# ecg_prototype_2.net
KiCad netlist of a schematic drawn in EAGLE
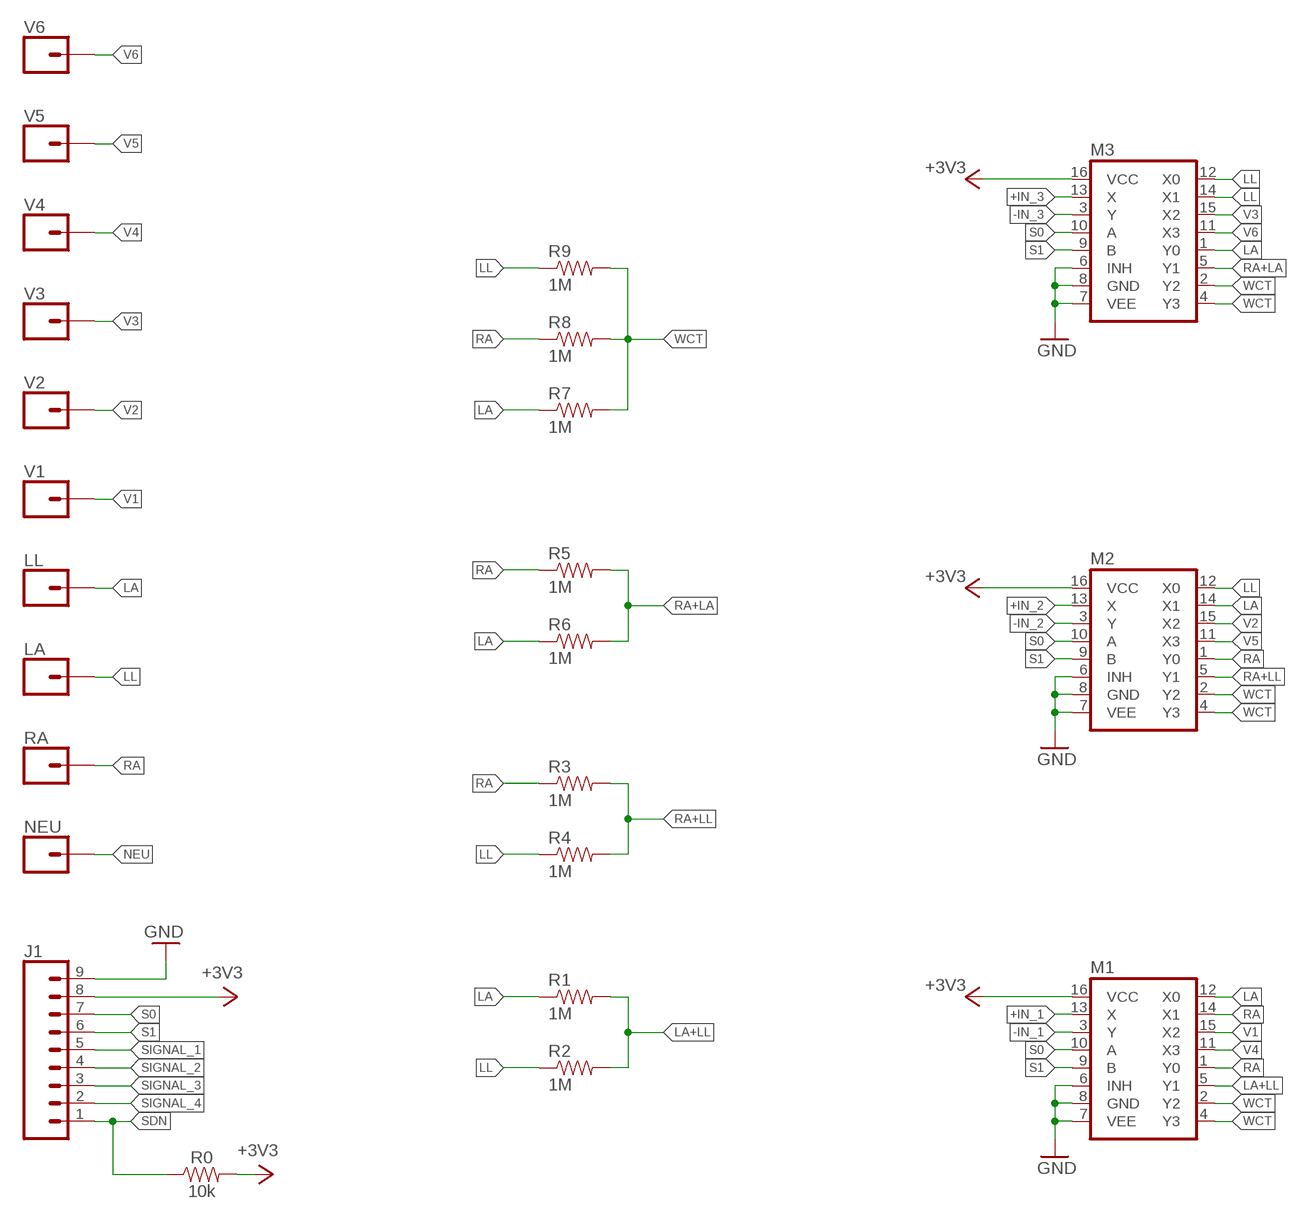
[diagram p0: schematic, sheet 1, part 1 of 2]
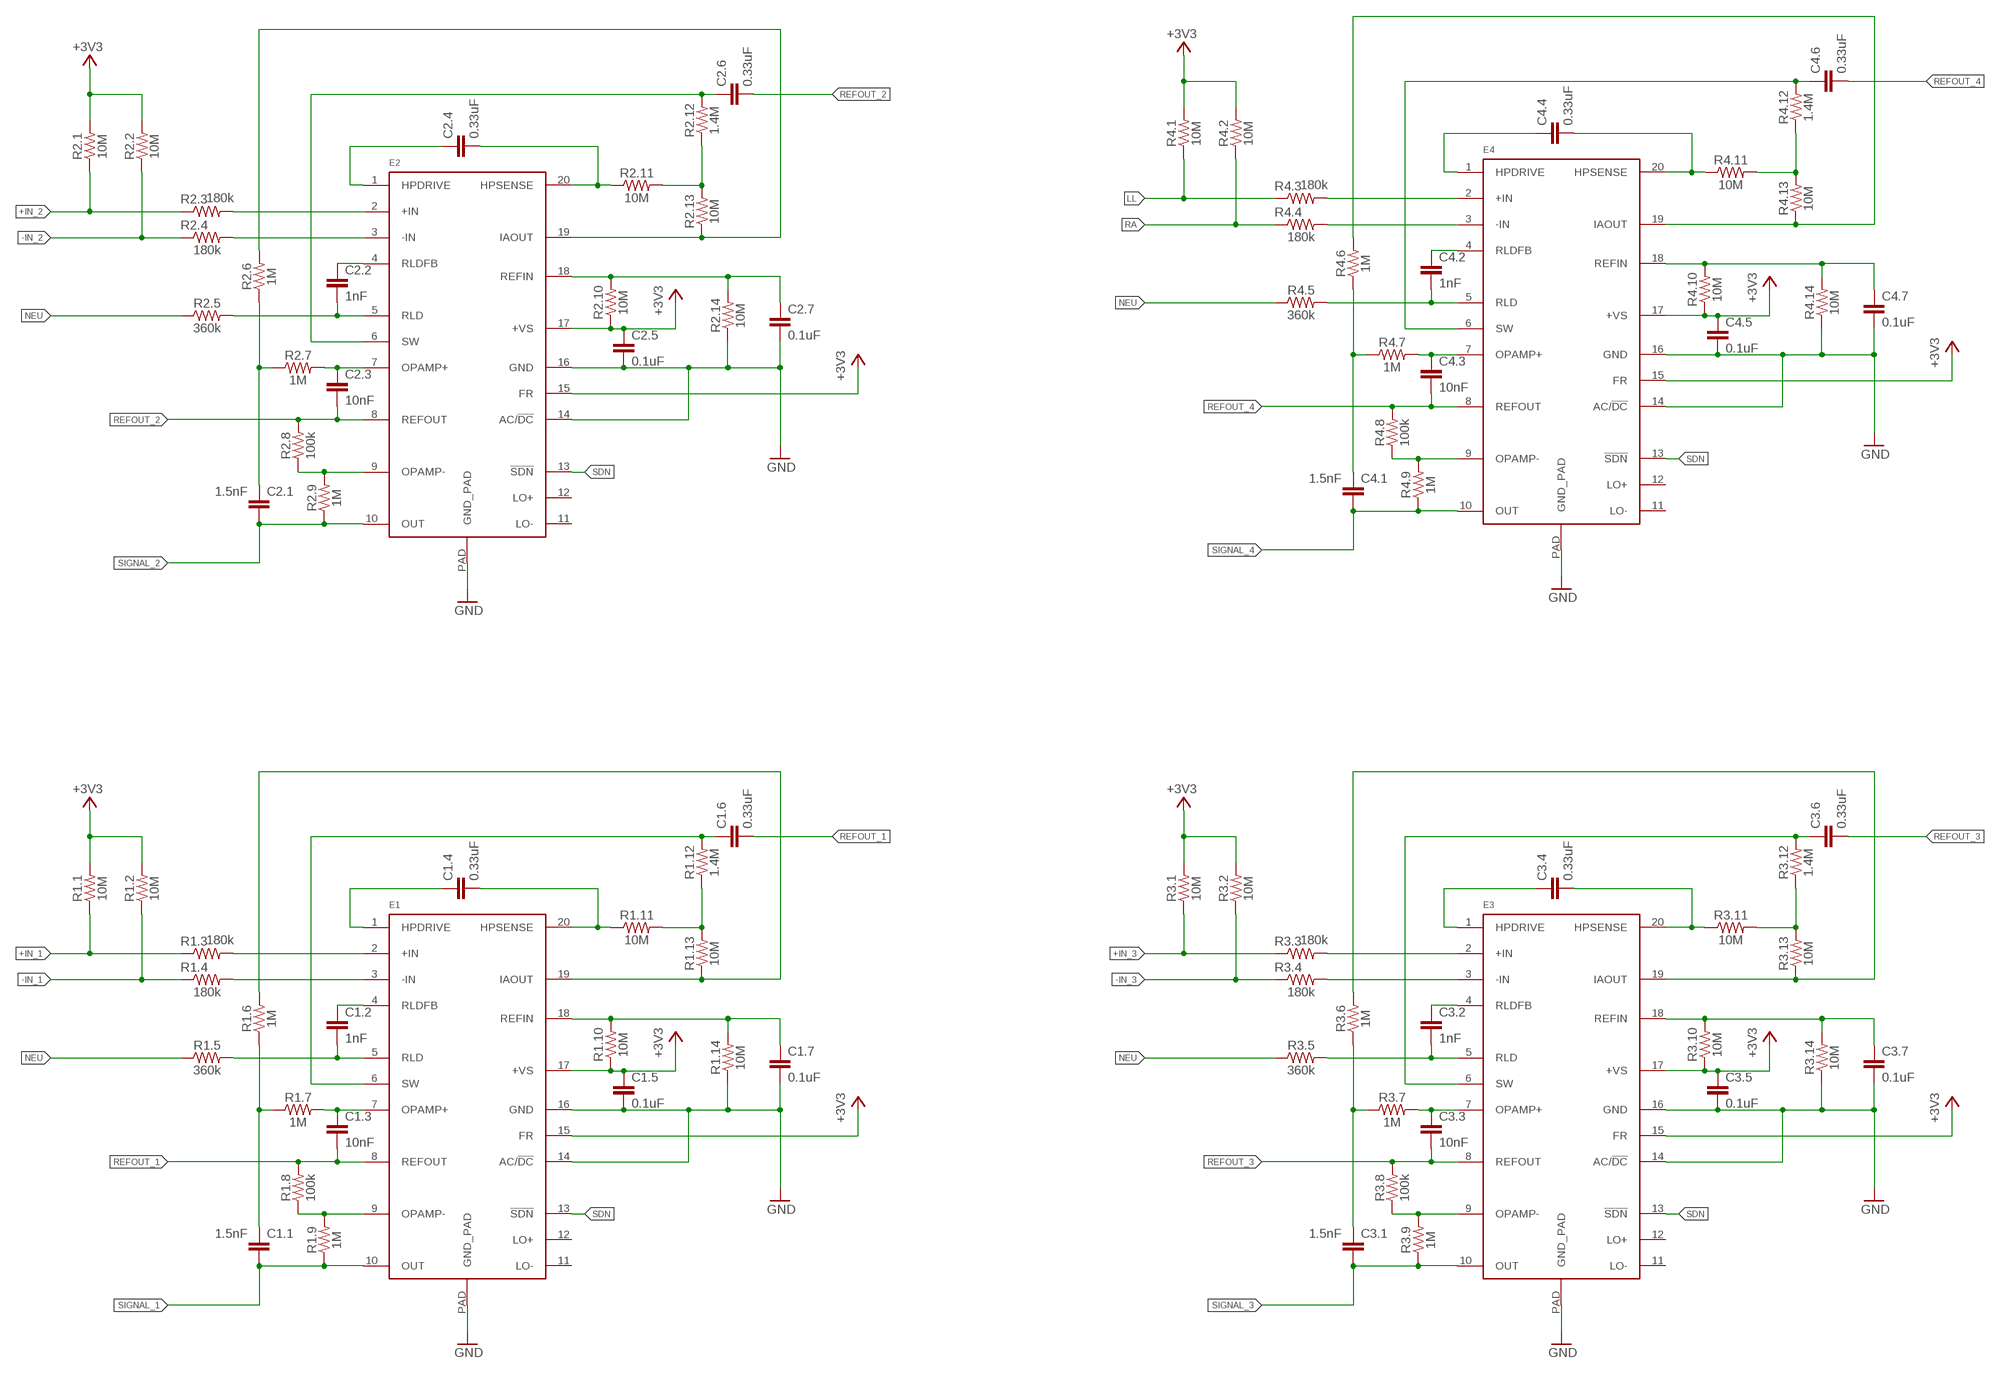
[diagram p1: schematic, sheet 1, part 2 of 2]

(export (version "E")
  (design (tool "Eeschema 10.0.6"))
  (components
    (comp (ref "C1.1")
      (value "1.5nF")
      (footprint "eagle-import:0603-CAP")
      (libsource (lib "eagle-import") (part "CAP0603-CAP"))
    )
    (comp (ref "C1.2")
      (value "1nF")
      (footprint "eagle-import:0603-CAP")
      (libsource (lib "eagle-import") (part "CAP0603-CAP"))
    )
    (comp (ref "C1.3")
      (value "10nF")
      (footprint "eagle-import:0603-CAP")
      (libsource (lib "eagle-import") (part "CAP0603-CAP"))
    )
    (comp (ref "C1.4")
      (value "0.33uF")
      (footprint "eagle-import:0805")
      (libsource (lib "eagle-import") (part "CAP0805"))
    )
    (comp (ref "C1.5")
      (value "0.1uF")
      (footprint "eagle-import:0603-CAP")
      (libsource (lib "eagle-import") (part "CAP0603-CAP"))
    )
    (comp (ref "C1.6")
      (value "0.33uF")
      (footprint "eagle-import:0805")
      (libsource (lib "eagle-import") (part "CAP0805"))
    )
    (comp (ref "C1.7")
      (value "0.1uF")
      (footprint "eagle-import:0603-CAP")
      (libsource (lib "eagle-import") (part "CAP0603-CAP"))
    )
    (comp (ref "C2.1")
      (value "1.5nF")
      (footprint "eagle-import:0603-CAP")
      (libsource (lib "eagle-import") (part "CAP0603-CAP"))
    )
    (comp (ref "C2.2")
      (value "1nF")
      (footprint "eagle-import:0603-CAP")
      (libsource (lib "eagle-import") (part "CAP0603-CAP"))
    )
    (comp (ref "C2.3")
      (value "10nF")
      (footprint "eagle-import:0603-CAP")
      (libsource (lib "eagle-import") (part "CAP0603-CAP"))
    )
    (comp (ref "C2.4")
      (value "0.33uF")
      (footprint "eagle-import:0805")
      (libsource (lib "eagle-import") (part "CAP0805"))
    )
    (comp (ref "C2.5")
      (value "0.1uF")
      (footprint "eagle-import:0603-CAP")
      (libsource (lib "eagle-import") (part "CAP0603-CAP"))
    )
    (comp (ref "C2.6")
      (value "0.33uF")
      (footprint "eagle-import:0805")
      (libsource (lib "eagle-import") (part "CAP0805"))
    )
    (comp (ref "C2.7")
      (value "0.1uF")
      (footprint "eagle-import:0603-CAP")
      (libsource (lib "eagle-import") (part "CAP0603-CAP"))
    )
    (comp (ref "C3.1")
      (value "1.5nF")
      (footprint "eagle-import:0603-CAP")
      (libsource (lib "eagle-import") (part "CAP0603-CAP"))
    )
    (comp (ref "C3.2")
      (value "1nF")
      (footprint "eagle-import:0603-CAP")
      (libsource (lib "eagle-import") (part "CAP0603-CAP"))
    )
    (comp (ref "C3.3")
      (value "10nF")
      (footprint "eagle-import:0603-CAP")
      (libsource (lib "eagle-import") (part "CAP0603-CAP"))
    )
    (comp (ref "C3.4")
      (value "0.33uF")
      (footprint "eagle-import:0805")
      (libsource (lib "eagle-import") (part "CAP0805"))
    )
    (comp (ref "C3.5")
      (value "0.1uF")
      (footprint "eagle-import:0603-CAP")
      (libsource (lib "eagle-import") (part "CAP0603-CAP"))
    )
    (comp (ref "C3.6")
      (value "0.33uF")
      (footprint "eagle-import:0805")
      (libsource (lib "eagle-import") (part "CAP0805"))
    )
    (comp (ref "C3.7")
      (value "0.1uF")
      (footprint "eagle-import:0603-CAP")
      (libsource (lib "eagle-import") (part "CAP0603-CAP"))
    )
    (comp (ref "C4.1")
      (value "1.5nF")
      (footprint "eagle-import:0603-CAP")
      (libsource (lib "eagle-import") (part "CAP0603-CAP"))
    )
    (comp (ref "C4.2")
      (value "1nF")
      (footprint "eagle-import:0603-CAP")
      (libsource (lib "eagle-import") (part "CAP0603-CAP"))
    )
    (comp (ref "C4.3")
      (value "10nF")
      (footprint "eagle-import:0603-CAP")
      (libsource (lib "eagle-import") (part "CAP0603-CAP"))
    )
    (comp (ref "C4.4")
      (value "0.33uF")
      (footprint "eagle-import:0805")
      (libsource (lib "eagle-import") (part "CAP0805"))
    )
    (comp (ref "C4.5")
      (value "0.1uF")
      (footprint "eagle-import:0603-CAP")
      (libsource (lib "eagle-import") (part "CAP0603-CAP"))
    )
    (comp (ref "C4.6")
      (value "0.33uF")
      (footprint "eagle-import:0805")
      (libsource (lib "eagle-import") (part "CAP0805"))
    )
    (comp (ref "C4.7")
      (value "0.1uF")
      (footprint "eagle-import:0603-CAP")
      (libsource (lib "eagle-import") (part "CAP0603-CAP"))
    )
    (comp (ref "E1")
      (value "AD8232ACPZ-R7")
      (footprint "eagle-import:LFCSP_20")
      (libsource (lib "eagle-import") (part "AD8232"))
    )
    (comp (ref "E2")
      (value "AD8232ACPZ-R7")
      (footprint "eagle-import:LFCSP_20")
      (libsource (lib "eagle-import") (part "AD8232"))
    )
    (comp (ref "E3")
      (value "AD8232ACPZ-R7")
      (footprint "eagle-import:LFCSP_20")
      (libsource (lib "eagle-import") (part "AD8232"))
    )
    (comp (ref "E4")
      (value "AD8232ACPZ-R7")
      (footprint "eagle-import:LFCSP_20")
      (libsource (lib "eagle-import") (part "AD8232"))
    )
    (comp (ref "J1")
      (value "CONN_09")
      (footprint "eagle-import:1X09")
      (libsource (lib "eagle-import") (part "CONN_09"))
    )
    (comp (ref "LA")
      (value "CONN_01")
      (footprint "eagle-import:1X01")
      (libsource (lib "eagle-import") (part "CONN_01"))
    )
    (comp (ref "LL")
      (value "CONN_01")
      (footprint "eagle-import:1X01")
      (libsource (lib "eagle-import") (part "CONN_01"))
    )
    (comp (ref "M1")
      (value "74HC4052D")
      (footprint "eagle-import:SO16")
      (libsource (lib "eagle-import") (part "744052DHC"))
    )
    (comp (ref "M2")
      (value "74HC4052D")
      (footprint "eagle-import:SO16")
      (libsource (lib "eagle-import") (part "744052DHC"))
    )
    (comp (ref "M3")
      (value "74HC4052D")
      (footprint "eagle-import:SO16")
      (libsource (lib "eagle-import") (part "744052DHC"))
    )
    (comp (ref "NEU")
      (value "CONN_01")
      (footprint "eagle-import:1X01")
      (libsource (lib "eagle-import") (part "CONN_01"))
    )
    (comp (ref "R0")
      (value "10k")
      (footprint "eagle-import:0603")
      (libsource (lib "eagle-import") (part "10KOHM-0603-1/10W-1%"))
    )
    (comp (ref "R1")
      (value "1M")
      (footprint "eagle-import:0402-RES")
      (libsource (lib "eagle-import") (part "RESISTOR0402-RES"))
    )
    (comp (ref "R1.1")
      (value "10M")
      (footprint "eagle-import:0603")
      (libsource (lib "eagle-import") (part "RESISTOR0603"))
    )
    (comp (ref "R1.2")
      (value "10M")
      (footprint "eagle-import:0603")
      (libsource (lib "eagle-import") (part "RESISTOR0603"))
    )
    (comp (ref "R1.3")
      (value "180k")
      (footprint "eagle-import:0603")
      (libsource (lib "eagle-import") (part "RESISTOR0603"))
    )
    (comp (ref "R1.4")
      (value "180k")
      (footprint "eagle-import:0603")
      (libsource (lib "eagle-import") (part "RESISTOR0603"))
    )
    (comp (ref "R1.5")
      (value "360k")
      (footprint "eagle-import:0603")
      (libsource (lib "eagle-import") (part "RESISTOR0603"))
    )
    (comp (ref "R1.6")
      (value "1M")
      (footprint "eagle-import:0603")
      (libsource (lib "eagle-import") (part "RESISTOR0603"))
    )
    (comp (ref "R1.7")
      (value "1M")
      (footprint "eagle-import:0603")
      (libsource (lib "eagle-import") (part "RESISTOR0603"))
    )
    (comp (ref "R1.8")
      (value "100k")
      (footprint "eagle-import:0603")
      (libsource (lib "eagle-import") (part "RESISTOR0603"))
    )
    (comp (ref "R1.9")
      (value "1M")
      (footprint "eagle-import:0603")
      (libsource (lib "eagle-import") (part "RESISTOR0603"))
    )
    (comp (ref "R1.10")
      (value "10M")
      (footprint "eagle-import:0603")
      (libsource (lib "eagle-import") (part "RESISTOR0603"))
    )
    (comp (ref "R1.11")
      (value "10M")
      (footprint "eagle-import:0603")
      (libsource (lib "eagle-import") (part "RESISTOR0603"))
    )
    (comp (ref "R1.12")
      (value "1.4M")
      (footprint "eagle-import:0603")
      (libsource (lib "eagle-import") (part "RESISTOR0603"))
    )
    (comp (ref "R1.13")
      (value "10M")
      (footprint "eagle-import:0603")
      (libsource (lib "eagle-import") (part "RESISTOR0603"))
    )
    (comp (ref "R1.14")
      (value "10M")
      (footprint "eagle-import:0603")
      (libsource (lib "eagle-import") (part "RESISTOR0603"))
    )
    (comp (ref "R2")
      (value "1M")
      (footprint "eagle-import:0402-RES")
      (libsource (lib "eagle-import") (part "RESISTOR0402-RES"))
    )
    (comp (ref "R2.1")
      (value "10M")
      (footprint "eagle-import:0603")
      (libsource (lib "eagle-import") (part "RESISTOR0603"))
    )
    (comp (ref "R2.2")
      (value "10M")
      (footprint "eagle-import:0603")
      (libsource (lib "eagle-import") (part "RESISTOR0603"))
    )
    (comp (ref "R2.3")
      (value "180k")
      (footprint "eagle-import:0603")
      (libsource (lib "eagle-import") (part "RESISTOR0603"))
    )
    (comp (ref "R2.4")
      (value "180k")
      (footprint "eagle-import:0603")
      (libsource (lib "eagle-import") (part "RESISTOR0603"))
    )
    (comp (ref "R2.5")
      (value "360k")
      (footprint "eagle-import:0603")
      (libsource (lib "eagle-import") (part "RESISTOR0603"))
    )
    (comp (ref "R2.6")
      (value "1M")
      (footprint "eagle-import:0603")
      (libsource (lib "eagle-import") (part "RESISTOR0603"))
    )
    (comp (ref "R2.7")
      (value "1M")
      (footprint "eagle-import:0603")
      (libsource (lib "eagle-import") (part "RESISTOR0603"))
    )
    (comp (ref "R2.8")
      (value "100k")
      (footprint "eagle-import:0603")
      (libsource (lib "eagle-import") (part "RESISTOR0603"))
    )
    (comp (ref "R2.9")
      (value "1M")
      (footprint "eagle-import:0603")
      (libsource (lib "eagle-import") (part "RESISTOR0603"))
    )
    (comp (ref "R2.10")
      (value "10M")
      (footprint "eagle-import:0603")
      (libsource (lib "eagle-import") (part "RESISTOR0603"))
    )
    (comp (ref "R2.11")
      (value "10M")
      (footprint "eagle-import:0603")
      (libsource (lib "eagle-import") (part "RESISTOR0603"))
    )
    (comp (ref "R2.12")
      (value "1.4M")
      (footprint "eagle-import:0603")
      (libsource (lib "eagle-import") (part "RESISTOR0603"))
    )
    (comp (ref "R2.13")
      (value "10M")
      (footprint "eagle-import:0603")
      (libsource (lib "eagle-import") (part "RESISTOR0603"))
    )
    (comp (ref "R2.14")
      (value "10M")
      (footprint "eagle-import:0603")
      (libsource (lib "eagle-import") (part "RESISTOR0603"))
    )
    (comp (ref "R3")
      (value "1M")
      (footprint "eagle-import:0402-RES")
      (libsource (lib "eagle-import") (part "RESISTOR0402-RES"))
    )
    (comp (ref "R3.1")
      (value "10M")
      (footprint "eagle-import:0603")
      (libsource (lib "eagle-import") (part "RESISTOR0603"))
    )
    (comp (ref "R3.2")
      (value "10M")
      (footprint "eagle-import:0603")
      (libsource (lib "eagle-import") (part "RESISTOR0603"))
    )
    (comp (ref "R3.3")
      (value "180k")
      (footprint "eagle-import:0603")
      (libsource (lib "eagle-import") (part "RESISTOR0603"))
    )
    (comp (ref "R3.4")
      (value "180k")
      (footprint "eagle-import:0603")
      (libsource (lib "eagle-import") (part "RESISTOR0603"))
    )
    (comp (ref "R3.5")
      (value "360k")
      (footprint "eagle-import:0603")
      (libsource (lib "eagle-import") (part "RESISTOR0603"))
    )
    (comp (ref "R3.6")
      (value "1M")
      (footprint "eagle-import:0603")
      (libsource (lib "eagle-import") (part "RESISTOR0603"))
    )
    (comp (ref "R3.7")
      (value "1M")
      (footprint "eagle-import:0603")
      (libsource (lib "eagle-import") (part "RESISTOR0603"))
    )
    (comp (ref "R3.8")
      (value "100k")
      (footprint "eagle-import:0603")
      (libsource (lib "eagle-import") (part "RESISTOR0603"))
    )
    (comp (ref "R3.9")
      (value "1M")
      (footprint "eagle-import:0603")
      (libsource (lib "eagle-import") (part "RESISTOR0603"))
    )
    (comp (ref "R3.10")
      (value "10M")
      (footprint "eagle-import:0603")
      (libsource (lib "eagle-import") (part "RESISTOR0603"))
    )
    (comp (ref "R3.11")
      (value "10M")
      (footprint "eagle-import:0603")
      (libsource (lib "eagle-import") (part "RESISTOR0603"))
    )
    (comp (ref "R3.12")
      (value "1.4M")
      (footprint "eagle-import:0603")
      (libsource (lib "eagle-import") (part "RESISTOR0603"))
    )
    (comp (ref "R3.13")
      (value "10M")
      (footprint "eagle-import:0603")
      (libsource (lib "eagle-import") (part "RESISTOR0603"))
    )
    (comp (ref "R3.14")
      (value "10M")
      (footprint "eagle-import:0603")
      (libsource (lib "eagle-import") (part "RESISTOR0603"))
    )
    (comp (ref "R4")
      (value "1M")
      (footprint "eagle-import:0402-RES")
      (libsource (lib "eagle-import") (part "RESISTOR0402-RES"))
    )
    (comp (ref "R4.1")
      (value "10M")
      (footprint "eagle-import:0603")
      (libsource (lib "eagle-import") (part "RESISTOR0603"))
    )
    (comp (ref "R4.2")
      (value "10M")
      (footprint "eagle-import:0603")
      (libsource (lib "eagle-import") (part "RESISTOR0603"))
    )
    (comp (ref "R4.3")
      (value "180k")
      (footprint "eagle-import:0603")
      (libsource (lib "eagle-import") (part "RESISTOR0603"))
    )
    (comp (ref "R4.4")
      (value "180k")
      (footprint "eagle-import:0603")
      (libsource (lib "eagle-import") (part "RESISTOR0603"))
    )
    (comp (ref "R4.5")
      (value "360k")
      (footprint "eagle-import:0603")
      (libsource (lib "eagle-import") (part "RESISTOR0603"))
    )
    (comp (ref "R4.6")
      (value "1M")
      (footprint "eagle-import:0603")
      (libsource (lib "eagle-import") (part "RESISTOR0603"))
    )
    (comp (ref "R4.7")
      (value "1M")
      (footprint "eagle-import:0603")
      (libsource (lib "eagle-import") (part "RESISTOR0603"))
    )
    (comp (ref "R4.8")
      (value "100k")
      (footprint "eagle-import:0603")
      (libsource (lib "eagle-import") (part "RESISTOR0603"))
    )
    (comp (ref "R4.9")
      (value "1M")
      (footprint "eagle-import:0603")
      (libsource (lib "eagle-import") (part "RESISTOR0603"))
    )
    (comp (ref "R4.10")
      (value "10M")
      (footprint "eagle-import:0603")
      (libsource (lib "eagle-import") (part "RESISTOR0603"))
    )
    (comp (ref "R4.11")
      (value "10M")
      (footprint "eagle-import:0603")
      (libsource (lib "eagle-import") (part "RESISTOR0603"))
    )
    (comp (ref "R4.12")
      (value "1.4M")
      (footprint "eagle-import:0603")
      (libsource (lib "eagle-import") (part "RESISTOR0603"))
    )
    (comp (ref "R4.13")
      (value "10M")
      (footprint "eagle-import:0603")
      (libsource (lib "eagle-import") (part "RESISTOR0603"))
    )
    (comp (ref "R4.14")
      (value "10M")
      (footprint "eagle-import:0603")
      (libsource (lib "eagle-import") (part "RESISTOR0603"))
    )
    (comp (ref "R5")
      (value "1M")
      (footprint "eagle-import:0402-RES")
      (libsource (lib "eagle-import") (part "RESISTOR0402-RES"))
    )
    (comp (ref "R6")
      (value "1M")
      (footprint "eagle-import:0402-RES")
      (libsource (lib "eagle-import") (part "RESISTOR0402-RES"))
    )
    (comp (ref "R7")
      (value "1M")
      (footprint "eagle-import:0402-RES")
      (libsource (lib "eagle-import") (part "RESISTOR0402-RES"))
    )
    (comp (ref "R8")
      (value "1M")
      (footprint "eagle-import:0402-RES")
      (libsource (lib "eagle-import") (part "RESISTOR0402-RES"))
    )
    (comp (ref "R9")
      (value "1M")
      (footprint "eagle-import:0402-RES")
      (libsource (lib "eagle-import") (part "RESISTOR0402-RES"))
    )
    (comp (ref "RA")
      (value "CONN_01")
      (footprint "eagle-import:1X01")
      (libsource (lib "eagle-import") (part "CONN_01"))
    )
    (comp (ref "V1")
      (value "CONN_01")
      (footprint "eagle-import:1X01")
      (libsource (lib "eagle-import") (part "CONN_01"))
    )
    (comp (ref "V2")
      (value "CONN_01")
      (footprint "eagle-import:1X01")
      (libsource (lib "eagle-import") (part "CONN_01"))
    )
    (comp (ref "V3")
      (value "CONN_01")
      (footprint "eagle-import:1X01")
      (libsource (lib "eagle-import") (part "CONN_01"))
    )
    (comp (ref "V4")
      (value "CONN_01")
      (footprint "eagle-import:1X01")
      (libsource (lib "eagle-import") (part "CONN_01"))
    )
    (comp (ref "V5")
      (value "CONN_01")
      (footprint "eagle-import:1X01")
      (libsource (lib "eagle-import") (part "CONN_01"))
    )
    (comp (ref "V6")
      (value "CONN_01")
      (footprint "eagle-import:1X01")
      (libsource (lib "eagle-import") (part "CONN_01"))
    )
  )
  (nets
    (net (code "1") (name "+3V3") (class "Default")
      (node (ref "C1.5") (pin "1") (pinfunction "1_1") (pintype "passive"))
      (node (ref "C2.5") (pin "1") (pinfunction "1_1") (pintype "passive"))
      (node (ref "C3.5") (pin "1") (pinfunction "1_1") (pintype "passive"))
      (node (ref "C4.5") (pin "1") (pinfunction "1_1") (pintype "passive"))
      (node (ref "E1") (pin "15") (pinfunction "FR_15") (pintype "bidirectional"))
      (node (ref "E1") (pin "17") (pinfunction "+VS_17") (pintype "bidirectional"))
      (node (ref "E2") (pin "15") (pinfunction "FR_15") (pintype "bidirectional"))
      (node (ref "E2") (pin "17") (pinfunction "+VS_17") (pintype "bidirectional"))
      (node (ref "E3") (pin "15") (pinfunction "FR_15") (pintype "bidirectional"))
      (node (ref "E3") (pin "17") (pinfunction "+VS_17") (pintype "bidirectional"))
      (node (ref "E4") (pin "15") (pinfunction "FR_15") (pintype "bidirectional"))
      (node (ref "E4") (pin "17") (pinfunction "+VS_17") (pintype "bidirectional"))
      (node (ref "J1") (pin "8") (pinfunction "8_8") (pintype "passive"))
      (node (ref "M1") (pin "16") (pinfunction "VCC_16") (pintype "power_in"))
      (node (ref "M2") (pin "16") (pinfunction "VCC_16") (pintype "power_in"))
      (node (ref "M3") (pin "16") (pinfunction "VCC_16") (pintype "power_in"))
      (node (ref "R0") (pin "2") (pinfunction "2_2") (pintype "passive"))
      (node (ref "R1.1") (pin "2") (pinfunction "2_2") (pintype "passive"))
      (node (ref "R1.10") (pin "1") (pinfunction "1_1") (pintype "passive"))
      (node (ref "R1.2") (pin "2") (pinfunction "2_2") (pintype "passive"))
      (node (ref "R2.1") (pin "2") (pinfunction "2_2") (pintype "passive"))
      (node (ref "R2.10") (pin "1") (pinfunction "1_1") (pintype "passive"))
      (node (ref "R2.2") (pin "2") (pinfunction "2_2") (pintype "passive"))
      (node (ref "R3.1") (pin "2") (pinfunction "2_2") (pintype "passive"))
      (node (ref "R3.10") (pin "1") (pinfunction "1_1") (pintype "passive"))
      (node (ref "R3.2") (pin "2") (pinfunction "2_2") (pintype "passive"))
      (node (ref "R4.1") (pin "2") (pinfunction "2_2") (pintype "passive"))
      (node (ref "R4.10") (pin "1") (pinfunction "1_1") (pintype "passive"))
      (node (ref "R4.2") (pin "2") (pinfunction "2_2") (pintype "passive"))
    )
    (net (code "2") (name "+IN_1") (class "Default")
      (node (ref "M1") (pin "13") (pinfunction "X_13") (pintype "bidirectional"))
      (node (ref "R1.1") (pin "1") (pinfunction "1_1") (pintype "passive"))
      (node (ref "R1.3") (pin "1") (pinfunction "1_1") (pintype "passive"))
    )
    (net (code "3") (name "+IN_2") (class "Default")
      (node (ref "M2") (pin "13") (pinfunction "X_13") (pintype "bidirectional"))
      (node (ref "R2.1") (pin "1") (pinfunction "1_1") (pintype "passive"))
      (node (ref "R2.3") (pin "1") (pinfunction "1_1") (pintype "passive"))
    )
    (net (code "4") (name "+IN_3") (class "Default")
      (node (ref "M3") (pin "13") (pinfunction "X_13") (pintype "bidirectional"))
      (node (ref "R3.1") (pin "1") (pinfunction "1_1") (pintype "passive"))
      (node (ref "R3.3") (pin "1") (pinfunction "1_1") (pintype "passive"))
    )
    (net (code "5") (name "-IN_1") (class "Default")
      (node (ref "M1") (pin "3") (pinfunction "Y_3") (pintype "bidirectional"))
      (node (ref "R1.2") (pin "1") (pinfunction "1_1") (pintype "passive"))
      (node (ref "R1.4") (pin "1") (pinfunction "1_1") (pintype "passive"))
    )
    (net (code "6") (name "-IN_2") (class "Default")
      (node (ref "M2") (pin "3") (pinfunction "Y_3") (pintype "bidirectional"))
      (node (ref "R2.2") (pin "1") (pinfunction "1_1") (pintype "passive"))
      (node (ref "R2.4") (pin "1") (pinfunction "1_1") (pintype "passive"))
    )
    (net (code "7") (name "-IN_3") (class "Default")
      (node (ref "M3") (pin "3") (pinfunction "Y_3") (pintype "bidirectional"))
      (node (ref "R3.2") (pin "1") (pinfunction "1_1") (pintype "passive"))
      (node (ref "R3.4") (pin "1") (pinfunction "1_1") (pintype "passive"))
    )
    (net (code "8") (name "GND") (class "Default")
      (node (ref "C1.5") (pin "2") (pinfunction "2_2") (pintype "passive"))
      (node (ref "C1.7") (pin "2") (pinfunction "2_2") (pintype "passive"))
      (node (ref "C2.5") (pin "2") (pinfunction "2_2") (pintype "passive"))
      (node (ref "C2.7") (pin "2") (pinfunction "2_2") (pintype "passive"))
      (node (ref "C3.5") (pin "2") (pinfunction "2_2") (pintype "passive"))
      (node (ref "C3.7") (pin "2") (pinfunction "2_2") (pintype "passive"))
      (node (ref "C4.5") (pin "2") (pinfunction "2_2") (pintype "passive"))
      (node (ref "C4.7") (pin "2") (pinfunction "2_2") (pintype "passive"))
      (node (ref "E1") (pin "14") (pinfunction "AC/~{DC}_14") (pintype "bidirectional"))
      (node (ref "E1") (pin "16") (pinfunction "GND_16") (pintype "bidirectional"))
      (node (ref "E1") (pin "PAD") (pinfunction "GND_PAD_PAD") (pintype "bidirectional"))
      (node (ref "E2") (pin "14") (pinfunction "AC/~{DC}_14") (pintype "bidirectional"))
      (node (ref "E2") (pin "16") (pinfunction "GND_16") (pintype "bidirectional"))
      (node (ref "E2") (pin "PAD") (pinfunction "GND_PAD_PAD") (pintype "bidirectional"))
      (node (ref "E3") (pin "14") (pinfunction "AC/~{DC}_14") (pintype "bidirectional"))
      (node (ref "E3") (pin "16") (pinfunction "GND_16") (pintype "bidirectional"))
      (node (ref "E3") (pin "PAD") (pinfunction "GND_PAD_PAD") (pintype "bidirectional"))
      (node (ref "E4") (pin "14") (pinfunction "AC/~{DC}_14") (pintype "bidirectional"))
      (node (ref "E4") (pin "16") (pinfunction "GND_16") (pintype "bidirectional"))
      (node (ref "E4") (pin "PAD") (pinfunction "GND_PAD_PAD") (pintype "bidirectional"))
      (node (ref "J1") (pin "9") (pinfunction "9_9") (pintype "passive"))
      (node (ref "M1") (pin "6") (pinfunction "INH_6") (pintype "input"))
      (node (ref "M1") (pin "7") (pinfunction "VEE_7") (pintype "power_in"))
      (node (ref "M1") (pin "8") (pinfunction "GND_8") (pintype "power_in"))
      (node (ref "M2") (pin "6") (pinfunction "INH_6") (pintype "input"))
      (node (ref "M2") (pin "7") (pinfunction "VEE_7") (pintype "power_in"))
      (node (ref "M2") (pin "8") (pinfunction "GND_8") (pintype "power_in"))
      (node (ref "M3") (pin "6") (pinfunction "INH_6") (pintype "input"))
      (node (ref "M3") (pin "7") (pinfunction "VEE_7") (pintype "power_in"))
      (node (ref "M3") (pin "8") (pinfunction "GND_8") (pintype "power_in"))
      (node (ref "R1.14") (pin "1") (pinfunction "1_1") (pintype "passive"))
      (node (ref "R2.14") (pin "1") (pinfunction "1_1") (pintype "passive"))
      (node (ref "R3.14") (pin "1") (pinfunction "1_1") (pintype "passive"))
      (node (ref "R4.14") (pin "1") (pinfunction "1_1") (pintype "passive"))
    )
    (net (code "9") (name "LA") (class "Default")
      (node (ref "LL") (pin "1") (pinfunction "1_1") (pintype "passive"))
      (node (ref "M1") (pin "12") (pinfunction "X0_12") (pintype "bidirectional"))
      (node (ref "M2") (pin "14") (pinfunction "X1_14") (pintype "bidirectional"))
      (node (ref "M3") (pin "1") (pinfunction "Y0_1") (pintype "bidirectional"))
      (node (ref "R1") (pin "1") (pinfunction "1_1") (pintype "passive"))
      (node (ref "R6") (pin "1") (pinfunction "1_1") (pintype "passive"))
      (node (ref "R7") (pin "1") (pinfunction "1_1") (pintype "passive"))
    )
    (net (code "10") (name "LA+LL") (class "Default")
      (node (ref "M1") (pin "5") (pinfunction "Y1_5") (pintype "bidirectional"))
      (node (ref "R1") (pin "2") (pinfunction "2_2") (pintype "passive"))
      (node (ref "R2") (pin "2") (pinfunction "2_2") (pintype "passive"))
    )
    (net (code "11") (name "LL") (class "Default")
      (node (ref "LA") (pin "1") (pinfunction "1_1") (pintype "passive"))
      (node (ref "M2") (pin "12") (pinfunction "X0_12") (pintype "bidirectional"))
      (node (ref "M3") (pin "12") (pinfunction "X0_12") (pintype "bidirectional"))
      (node (ref "M3") (pin "14") (pinfunction "X1_14") (pintype "bidirectional"))
      (node (ref "R2") (pin "1") (pinfunction "1_1") (pintype "passive"))
      (node (ref "R4") (pin "1") (pinfunction "1_1") (pintype "passive"))
      (node (ref "R4.1") (pin "1") (pinfunction "1_1") (pintype "passive"))
      (node (ref "R4.3") (pin "1") (pinfunction "1_1") (pintype "passive"))
      (node (ref "R9") (pin "1") (pinfunction "1_1") (pintype "passive"))
    )
    (net (code "12") (name "NEU") (class "Default")
      (node (ref "NEU") (pin "1") (pinfunction "1_1") (pintype "passive"))
      (node (ref "R1.5") (pin "1") (pinfunction "1_1") (pintype "passive"))
      (node (ref "R2.5") (pin "1") (pinfunction "1_1") (pintype "passive"))
      (node (ref "R3.5") (pin "1") (pinfunction "1_1") (pintype "passive"))
      (node (ref "R4.5") (pin "1") (pinfunction "1_1") (pintype "passive"))
    )
    (net (code "13") (name "Net-(C1.1-Pad1)") (class "Default")
      (node (ref "C1.1") (pin "1") (pinfunction "1_1") (pintype "passive"))
      (node (ref "R1.6") (pin "1") (pinfunction "1_1") (pintype "passive"))
      (node (ref "R1.7") (pin "1") (pinfunction "1_1") (pintype "passive"))
    )
    (net (code "14") (name "Net-(C2.1-Pad1)") (class "Default")
      (node (ref "C2.1") (pin "1") (pinfunction "1_1") (pintype "passive"))
      (node (ref "R2.6") (pin "1") (pinfunction "1_1") (pintype "passive"))
      (node (ref "R2.7") (pin "1") (pinfunction "1_1") (pintype "passive"))
    )
    (net (code "15") (name "Net-(C3.1-Pad1)") (class "Default")
      (node (ref "C3.1") (pin "1") (pinfunction "1_1") (pintype "passive"))
      (node (ref "R3.6") (pin "1") (pinfunction "1_1") (pintype "passive"))
      (node (ref "R3.7") (pin "1") (pinfunction "1_1") (pintype "passive"))
    )
    (net (code "16") (name "Net-(C4.1-Pad1)") (class "Default")
      (node (ref "C4.1") (pin "1") (pinfunction "1_1") (pintype "passive"))
      (node (ref "R4.6") (pin "1") (pinfunction "1_1") (pintype "passive"))
      (node (ref "R4.7") (pin "1") (pinfunction "1_1") (pintype "passive"))
    )
    (net (code "17") (name "Net-(E1-+IN)") (class "Default")
      (node (ref "E1") (pin "2") (pinfunction "+IN_2") (pintype "bidirectional"))
      (node (ref "R1.3") (pin "2") (pinfunction "2_2") (pintype "passive"))
    )
    (net (code "18") (name "Net-(E1--IN)") (class "Default")
      (node (ref "E1") (pin "3") (pinfunction "-IN_3") (pintype "bidirectional"))
      (node (ref "R1.4") (pin "2") (pinfunction "2_2") (pintype "passive"))
    )
    (net (code "19") (name "Net-(E1-HPDRIVE)") (class "Default")
      (node (ref "C1.4") (pin "1") (pinfunction "1_1") (pintype "passive"))
      (node (ref "E1") (pin "1") (pinfunction "HPDRIVE_1") (pintype "bidirectional"))
    )
    (net (code "20") (name "Net-(E1-HPSENSE)") (class "Default")
      (node (ref "C1.4") (pin "2") (pinfunction "2_2") (pintype "passive"))
      (node (ref "E1") (pin "20") (pinfunction "HPSENSE_20") (pintype "bidirectional"))
      (node (ref "R1.11") (pin "1") (pinfunction "1_1") (pintype "passive"))
    )
    (net (code "21") (name "Net-(E1-IAOUT)") (class "Default")
      (node (ref "E1") (pin "19") (pinfunction "IAOUT_19") (pintype "bidirectional"))
      (node (ref "R1.13") (pin "1") (pinfunction "1_1") (pintype "passive"))
      (node (ref "R1.6") (pin "2") (pinfunction "2_2") (pintype "passive"))
    )
    (net (code "22") (name "Net-(E1-OPAMP+)") (class "Default")
      (node (ref "C1.3") (pin "1") (pinfunction "1_1") (pintype "passive"))
      (node (ref "E1") (pin "7") (pinfunction "OPAMP+_7") (pintype "bidirectional"))
      (node (ref "R1.7") (pin "2") (pinfunction "2_2") (pintype "passive"))
    )
    (net (code "23") (name "Net-(E1-OPAMP-)") (class "Default")
      (node (ref "E1") (pin "9") (pinfunction "OPAMP-_9") (pintype "bidirectional"))
      (node (ref "R1.8") (pin "1") (pinfunction "1_1") (pintype "passive"))
      (node (ref "R1.9") (pin "2") (pinfunction "2_2") (pintype "passive"))
    )
    (net (code "24") (name "Net-(E1-REFIN)") (class "Default")
      (node (ref "C1.7") (pin "1") (pinfunction "1_1") (pintype "passive"))
      (node (ref "E1") (pin "18") (pinfunction "REFIN_18") (pintype "bidirectional"))
      (node (ref "R1.10") (pin "2") (pinfunction "2_2") (pintype "passive"))
      (node (ref "R1.14") (pin "2") (pinfunction "2_2") (pintype "passive"))
    )
    (net (code "25") (name "Net-(E1-RLD)") (class "Default")
      (node (ref "C1.2") (pin "2") (pinfunction "2_2") (pintype "passive"))
      (node (ref "E1") (pin "5") (pinfunction "RLD_5") (pintype "bidirectional"))
      (node (ref "R1.5") (pin "2") (pinfunction "2_2") (pintype "passive"))
    )
    (net (code "26") (name "Net-(E1-RLDFB)") (class "Default")
      (node (ref "C1.2") (pin "1") (pinfunction "1_1") (pintype "passive"))
      (node (ref "E1") (pin "4") (pinfunction "RLDFB_4") (pintype "bidirectional"))
    )
    (net (code "27") (name "Net-(E1-SW)") (class "Default")
      (node (ref "C1.6") (pin "1") (pinfunction "1_1") (pintype "passive"))
      (node (ref "E1") (pin "6") (pinfunction "SW_6") (pintype "bidirectional"))
      (node (ref "R1.12") (pin "2") (pinfunction "2_2") (pintype "passive"))
    )
    (net (code "28") (name "Net-(E2-+IN)") (class "Default")
      (node (ref "E2") (pin "2") (pinfunction "+IN_2") (pintype "bidirectional"))
      (node (ref "R2.3") (pin "2") (pinfunction "2_2") (pintype "passive"))
    )
    (net (code "29") (name "Net-(E2--IN)") (class "Default")
      (node (ref "E2") (pin "3") (pinfunction "-IN_3") (pintype "bidirectional"))
      (node (ref "R2.4") (pin "2") (pinfunction "2_2") (pintype "passive"))
    )
    (net (code "30") (name "Net-(E2-HPDRIVE)") (class "Default")
      (node (ref "C2.4") (pin "1") (pinfunction "1_1") (pintype "passive"))
      (node (ref "E2") (pin "1") (pinfunction "HPDRIVE_1") (pintype "bidirectional"))
    )
    (net (code "31") (name "Net-(E2-HPSENSE)") (class "Default")
      (node (ref "C2.4") (pin "2") (pinfunction "2_2") (pintype "passive"))
      (node (ref "E2") (pin "20") (pinfunction "HPSENSE_20") (pintype "bidirectional"))
      (node (ref "R2.11") (pin "1") (pinfunction "1_1") (pintype "passive"))
    )
    (net (code "32") (name "Net-(E2-IAOUT)") (class "Default")
      (node (ref "E2") (pin "19") (pinfunction "IAOUT_19") (pintype "bidirectional"))
      (node (ref "R2.13") (pin "1") (pinfunction "1_1") (pintype "passive"))
      (node (ref "R2.6") (pin "2") (pinfunction "2_2") (pintype "passive"))
    )
    (net (code "33") (name "Net-(E2-OPAMP+)") (class "Default")
      (node (ref "C2.3") (pin "1") (pinfunction "1_1") (pintype "passive"))
      (node (ref "E2") (pin "7") (pinfunction "OPAMP+_7") (pintype "bidirectional"))
      (node (ref "R2.7") (pin "2") (pinfunction "2_2") (pintype "passive"))
    )
    (net (code "34") (name "Net-(E2-OPAMP-)") (class "Default")
      (node (ref "E2") (pin "9") (pinfunction "OPAMP-_9") (pintype "bidirectional"))
      (node (ref "R2.8") (pin "1") (pinfunction "1_1") (pintype "passive"))
      (node (ref "R2.9") (pin "2") (pinfunction "2_2") (pintype "passive"))
    )
    (net (code "35") (name "Net-(E2-REFIN)") (class "Default")
      (node (ref "C2.7") (pin "1") (pinfunction "1_1") (pintype "passive"))
      (node (ref "E2") (pin "18") (pinfunction "REFIN_18") (pintype "bidirectional"))
      (node (ref "R2.10") (pin "2") (pinfunction "2_2") (pintype "passive"))
      (node (ref "R2.14") (pin "2") (pinfunction "2_2") (pintype "passive"))
    )
    (net (code "36") (name "Net-(E2-RLD)") (class "Default")
      (node (ref "C2.2") (pin "2") (pinfunction "2_2") (pintype "passive"))
      (node (ref "E2") (pin "5") (pinfunction "RLD_5") (pintype "bidirectional"))
      (node (ref "R2.5") (pin "2") (pinfunction "2_2") (pintype "passive"))
    )
    (net (code "37") (name "Net-(E2-RLDFB)") (class "Default")
      (node (ref "C2.2") (pin "1") (pinfunction "1_1") (pintype "passive"))
      (node (ref "E2") (pin "4") (pinfunction "RLDFB_4") (pintype "bidirectional"))
    )
    (net (code "38") (name "Net-(E2-SW)") (class "Default")
      (node (ref "C2.6") (pin "1") (pinfunction "1_1") (pintype "passive"))
      (node (ref "E2") (pin "6") (pinfunction "SW_6") (pintype "bidirectional"))
      (node (ref "R2.12") (pin "2") (pinfunction "2_2") (pintype "passive"))
    )
    (net (code "39") (name "Net-(E3-+IN)") (class "Default")
      (node (ref "E3") (pin "2") (pinfunction "+IN_2") (pintype "bidirectional"))
      (node (ref "R3.3") (pin "2") (pinfunction "2_2") (pintype "passive"))
    )
    (net (code "40") (name "Net-(E3--IN)") (class "Default")
      (node (ref "E3") (pin "3") (pinfunction "-IN_3") (pintype "bidirectional"))
      (node (ref "R3.4") (pin "2") (pinfunction "2_2") (pintype "passive"))
    )
    (net (code "41") (name "Net-(E3-HPDRIVE)") (class "Default")
      (node (ref "C3.4") (pin "1") (pinfunction "1_1") (pintype "passive"))
      (node (ref "E3") (pin "1") (pinfunction "HPDRIVE_1") (pintype "bidirectional"))
    )
    (net (code "42") (name "Net-(E3-HPSENSE)") (class "Default")
      (node (ref "C3.4") (pin "2") (pinfunction "2_2") (pintype "passive"))
      (node (ref "E3") (pin "20") (pinfunction "HPSENSE_20") (pintype "bidirectional"))
      (node (ref "R3.11") (pin "1") (pinfunction "1_1") (pintype "passive"))
    )
    (net (code "43") (name "Net-(E3-IAOUT)") (class "Default")
      (node (ref "E3") (pin "19") (pinfunction "IAOUT_19") (pintype "bidirectional"))
      (node (ref "R3.13") (pin "1") (pinfunction "1_1") (pintype "passive"))
      (node (ref "R3.6") (pin "2") (pinfunction "2_2") (pintype "passive"))
    )
    (net (code "44") (name "Net-(E3-OPAMP+)") (class "Default")
      (node (ref "C3.3") (pin "1") (pinfunction "1_1") (pintype "passive"))
      (node (ref "E3") (pin "7") (pinfunction "OPAMP+_7") (pintype "bidirectional"))
      (node (ref "R3.7") (pin "2") (pinfunction "2_2") (pintype "passive"))
    )
    (net (code "45") (name "Net-(E3-OPAMP-)") (class "Default")
      (node (ref "E3") (pin "9") (pinfunction "OPAMP-_9") (pintype "bidirectional"))
      (node (ref "R3.8") (pin "1") (pinfunction "1_1") (pintype "passive"))
      (node (ref "R3.9") (pin "2") (pinfunction "2_2") (pintype "passive"))
    )
    (net (code "46") (name "Net-(E3-REFIN)") (class "Default")
      (node (ref "C3.7") (pin "1") (pinfunction "1_1") (pintype "passive"))
      (node (ref "E3") (pin "18") (pinfunction "REFIN_18") (pintype "bidirectional"))
      (node (ref "R3.10") (pin "2") (pinfunction "2_2") (pintype "passive"))
      (node (ref "R3.14") (pin "2") (pinfunction "2_2") (pintype "passive"))
    )
    (net (code "47") (name "Net-(E3-RLD)") (class "Default")
      (node (ref "C3.2") (pin "2") (pinfunction "2_2") (pintype "passive"))
      (node (ref "E3") (pin "5") (pinfunction "RLD_5") (pintype "bidirectional"))
      (node (ref "R3.5") (pin "2") (pinfunction "2_2") (pintype "passive"))
    )
    (net (code "48") (name "Net-(E3-RLDFB)") (class "Default")
      (node (ref "C3.2") (pin "1") (pinfunction "1_1") (pintype "passive"))
      (node (ref "E3") (pin "4") (pinfunction "RLDFB_4") (pintype "bidirectional"))
    )
    (net (code "49") (name "Net-(E3-SW)") (class "Default")
      (node (ref "C3.6") (pin "1") (pinfunction "1_1") (pintype "passive"))
      (node (ref "E3") (pin "6") (pinfunction "SW_6") (pintype "bidirectional"))
      (node (ref "R3.12") (pin "2") (pinfunction "2_2") (pintype "passive"))
    )
    (net (code "50") (name "Net-(E4-+IN)") (class "Default")
      (node (ref "E4") (pin "2") (pinfunction "+IN_2") (pintype "bidirectional"))
      (node (ref "R4.3") (pin "2") (pinfunction "2_2") (pintype "passive"))
    )
    (net (code "51") (name "Net-(E4--IN)") (class "Default")
      (node (ref "E4") (pin "3") (pinfunction "-IN_3") (pintype "bidirectional"))
      (node (ref "R4.4") (pin "2") (pinfunction "2_2") (pintype "passive"))
    )
    (net (code "52") (name "Net-(E4-HPDRIVE)") (class "Default")
      (node (ref "C4.4") (pin "1") (pinfunction "1_1") (pintype "passive"))
      (node (ref "E4") (pin "1") (pinfunction "HPDRIVE_1") (pintype "bidirectional"))
    )
    (net (code "53") (name "Net-(E4-HPSENSE)") (class "Default")
      (node (ref "C4.4") (pin "2") (pinfunction "2_2") (pintype "passive"))
      (node (ref "E4") (pin "20") (pinfunction "HPSENSE_20") (pintype "bidirectional"))
      (node (ref "R4.11") (pin "1") (pinfunction "1_1") (pintype "passive"))
    )
    (net (code "54") (name "Net-(E4-IAOUT)") (class "Default")
      (node (ref "E4") (pin "19") (pinfunction "IAOUT_19") (pintype "bidirectional"))
      (node (ref "R4.13") (pin "1") (pinfunction "1_1") (pintype "passive"))
      (node (ref "R4.6") (pin "2") (pinfunction "2_2") (pintype "passive"))
    )
    (net (code "55") (name "Net-(E4-OPAMP+)") (class "Default")
      (node (ref "C4.3") (pin "1") (pinfunction "1_1") (pintype "passive"))
      (node (ref "E4") (pin "7") (pinfunction "OPAMP+_7") (pintype "bidirectional"))
      (node (ref "R4.7") (pin "2") (pinfunction "2_2") (pintype "passive"))
    )
    (net (code "56") (name "Net-(E4-OPAMP-)") (class "Default")
      (node (ref "E4") (pin "9") (pinfunction "OPAMP-_9") (pintype "bidirectional"))
      (node (ref "R4.8") (pin "1") (pinfunction "1_1") (pintype "passive"))
      (node (ref "R4.9") (pin "2") (pinfunction "2_2") (pintype "passive"))
    )
    (net (code "57") (name "Net-(E4-REFIN)") (class "Default")
      (node (ref "C4.7") (pin "1") (pinfunction "1_1") (pintype "passive"))
      (node (ref "E4") (pin "18") (pinfunction "REFIN_18") (pintype "bidirectional"))
      (node (ref "R4.10") (pin "2") (pinfunction "2_2") (pintype "passive"))
      (node (ref "R4.14") (pin "2") (pinfunction "2_2") (pintype "passive"))
    )
    (net (code "58") (name "Net-(E4-RLD)") (class "Default")
      (node (ref "C4.2") (pin "2") (pinfunction "2_2") (pintype "passive"))
      (node (ref "E4") (pin "5") (pinfunction "RLD_5") (pintype "bidirectional"))
      (node (ref "R4.5") (pin "2") (pinfunction "2_2") (pintype "passive"))
    )
    (net (code "59") (name "Net-(E4-RLDFB)") (class "Default")
      (node (ref "C4.2") (pin "1") (pinfunction "1_1") (pintype "passive"))
      (node (ref "E4") (pin "4") (pinfunction "RLDFB_4") (pintype "bidirectional"))
    )
    (net (code "60") (name "Net-(E4-SW)") (class "Default")
      (node (ref "C4.6") (pin "1") (pinfunction "1_1") (pintype "passive"))
      (node (ref "E4") (pin "6") (pinfunction "SW_6") (pintype "bidirectional"))
      (node (ref "R4.12") (pin "2") (pinfunction "2_2") (pintype "passive"))
    )
    (net (code "61") (name "Net-(R1.11-Pad2)") (class "Default")
      (node (ref "R1.11") (pin "2") (pinfunction "2_2") (pintype "passive"))
      (node (ref "R1.12") (pin "1") (pinfunction "1_1") (pintype "passive"))
      (node (ref "R1.13") (pin "2") (pinfunction "2_2") (pintype "passive"))
    )
    (net (code "62") (name "Net-(R2.11-Pad2)") (class "Default")
      (node (ref "R2.11") (pin "2") (pinfunction "2_2") (pintype "passive"))
      (node (ref "R2.12") (pin "1") (pinfunction "1_1") (pintype "passive"))
      (node (ref "R2.13") (pin "2") (pinfunction "2_2") (pintype "passive"))
    )
    (net (code "63") (name "Net-(R3.11-Pad2)") (class "Default")
      (node (ref "R3.11") (pin "2") (pinfunction "2_2") (pintype "passive"))
      (node (ref "R3.12") (pin "1") (pinfunction "1_1") (pintype "passive"))
      (node (ref "R3.13") (pin "2") (pinfunction "2_2") (pintype "passive"))
    )
    (net (code "64") (name "Net-(R4.11-Pad2)") (class "Default")
      (node (ref "R4.11") (pin "2") (pinfunction "2_2") (pintype "passive"))
      (node (ref "R4.12") (pin "1") (pinfunction "1_1") (pintype "passive"))
      (node (ref "R4.13") (pin "2") (pinfunction "2_2") (pintype "passive"))
    )
    (net (code "65") (name "RA") (class "Default")
      (node (ref "M1") (pin "1") (pinfunction "Y0_1") (pintype "bidirectional"))
      (node (ref "M1") (pin "14") (pinfunction "X1_14") (pintype "bidirectional"))
      (node (ref "M2") (pin "1") (pinfunction "Y0_1") (pintype "bidirectional"))
      (node (ref "R3") (pin "1") (pinfunction "1_1") (pintype "passive"))
      (node (ref "R4.2") (pin "1") (pinfunction "1_1") (pintype "passive"))
      (node (ref "R4.4") (pin "1") (pinfunction "1_1") (pintype "passive"))
      (node (ref "R5") (pin "1") (pinfunction "1_1") (pintype "passive"))
      (node (ref "R8") (pin "1") (pinfunction "1_1") (pintype "passive"))
      (node (ref "RA") (pin "1") (pinfunction "1_1") (pintype "passive"))
    )
    (net (code "66") (name "RA+LA") (class "Default")
      (node (ref "M3") (pin "5") (pinfunction "Y1_5") (pintype "bidirectional"))
      (node (ref "R5") (pin "2") (pinfunction "2_2") (pintype "passive"))
      (node (ref "R6") (pin "2") (pinfunction "2_2") (pintype "passive"))
    )
    (net (code "67") (name "RA+LL") (class "Default")
      (node (ref "M2") (pin "5") (pinfunction "Y1_5") (pintype "bidirectional"))
      (node (ref "R3") (pin "2") (pinfunction "2_2") (pintype "passive"))
      (node (ref "R4") (pin "2") (pinfunction "2_2") (pintype "passive"))
    )
    (net (code "68") (name "REFOUT_1") (class "Default")
      (node (ref "C1.3") (pin "2") (pinfunction "2_2") (pintype "passive"))
      (node (ref "C1.6") (pin "2") (pinfunction "2_2") (pintype "passive"))
      (node (ref "E1") (pin "8") (pinfunction "REFOUT_8") (pintype "bidirectional"))
      (node (ref "R1.8") (pin "2") (pinfunction "2_2") (pintype "passive"))
    )
    (net (code "69") (name "REFOUT_2") (class "Default")
      (node (ref "C2.3") (pin "2") (pinfunction "2_2") (pintype "passive"))
      (node (ref "C2.6") (pin "2") (pinfunction "2_2") (pintype "passive"))
      (node (ref "E2") (pin "8") (pinfunction "REFOUT_8") (pintype "bidirectional"))
      (node (ref "R2.8") (pin "2") (pinfunction "2_2") (pintype "passive"))
    )
    (net (code "70") (name "REFOUT_3") (class "Default")
      (node (ref "C3.3") (pin "2") (pinfunction "2_2") (pintype "passive"))
      (node (ref "C3.6") (pin "2") (pinfunction "2_2") (pintype "passive"))
      (node (ref "E3") (pin "8") (pinfunction "REFOUT_8") (pintype "bidirectional"))
      (node (ref "R3.8") (pin "2") (pinfunction "2_2") (pintype "passive"))
    )
    (net (code "71") (name "REFOUT_4") (class "Default")
      (node (ref "C4.3") (pin "2") (pinfunction "2_2") (pintype "passive"))
      (node (ref "C4.6") (pin "2") (pinfunction "2_2") (pintype "passive"))
      (node (ref "E4") (pin "8") (pinfunction "REFOUT_8") (pintype "bidirectional"))
      (node (ref "R4.8") (pin "2") (pinfunction "2_2") (pintype "passive"))
    )
    (net (code "72") (name "S0") (class "Default")
      (node (ref "J1") (pin "7") (pinfunction "7_7") (pintype "passive"))
      (node (ref "M1") (pin "10") (pinfunction "A_10") (pintype "input"))
      (node (ref "M2") (pin "10") (pinfunction "A_10") (pintype "input"))
      (node (ref "M3") (pin "10") (pinfunction "A_10") (pintype "input"))
    )
    (net (code "73") (name "S1") (class "Default")
      (node (ref "J1") (pin "6") (pinfunction "6_6") (pintype "passive"))
      (node (ref "M1") (pin "9") (pinfunction "B_9") (pintype "input"))
      (node (ref "M2") (pin "9") (pinfunction "B_9") (pintype "input"))
      (node (ref "M3") (pin "9") (pinfunction "B_9") (pintype "input"))
    )
    (net (code "74") (name "SDN") (class "Default")
      (node (ref "E1") (pin "13") (pinfunction "~{SDN}_13") (pintype "bidirectional"))
      (node (ref "E2") (pin "13") (pinfunction "~{SDN}_13") (pintype "bidirectional"))
      (node (ref "E3") (pin "13") (pinfunction "~{SDN}_13") (pintype "bidirectional"))
      (node (ref "E4") (pin "13") (pinfunction "~{SDN}_13") (pintype "bidirectional"))
      (node (ref "J1") (pin "1") (pinfunction "1_1") (pintype "passive"))
      (node (ref "R0") (pin "1") (pinfunction "1_1") (pintype "passive"))
    )
    (net (code "75") (name "SIGNAL_1") (class "Default")
      (node (ref "C1.1") (pin "2") (pinfunction "2_2") (pintype "passive"))
      (node (ref "E1") (pin "10") (pinfunction "OUT_10") (pintype "bidirectional"))
      (node (ref "J1") (pin "5") (pinfunction "5_5") (pintype "passive"))
      (node (ref "R1.9") (pin "1") (pinfunction "1_1") (pintype "passive"))
    )
    (net (code "76") (name "SIGNAL_2") (class "Default")
      (node (ref "C2.1") (pin "2") (pinfunction "2_2") (pintype "passive"))
      (node (ref "E2") (pin "10") (pinfunction "OUT_10") (pintype "bidirectional"))
      (node (ref "J1") (pin "4") (pinfunction "4_4") (pintype "passive"))
      (node (ref "R2.9") (pin "1") (pinfunction "1_1") (pintype "passive"))
    )
    (net (code "77") (name "SIGNAL_3") (class "Default")
      (node (ref "C3.1") (pin "2") (pinfunction "2_2") (pintype "passive"))
      (node (ref "E3") (pin "10") (pinfunction "OUT_10") (pintype "bidirectional"))
      (node (ref "J1") (pin "3") (pinfunction "3_3") (pintype "passive"))
      (node (ref "R3.9") (pin "1") (pinfunction "1_1") (pintype "passive"))
    )
    (net (code "78") (name "SIGNAL_4") (class "Default")
      (node (ref "C4.1") (pin "2") (pinfunction "2_2") (pintype "passive"))
      (node (ref "E4") (pin "10") (pinfunction "OUT_10") (pintype "bidirectional"))
      (node (ref "J1") (pin "2") (pinfunction "2_2") (pintype "passive"))
      (node (ref "R4.9") (pin "1") (pinfunction "1_1") (pintype "passive"))
    )
    (net (code "79") (name "V1") (class "Default")
      (node (ref "M1") (pin "15") (pinfunction "X2_15") (pintype "bidirectional"))
      (node (ref "V1") (pin "1") (pinfunction "1_1") (pintype "passive"))
    )
    (net (code "80") (name "V2") (class "Default")
      (node (ref "M2") (pin "15") (pinfunction "X2_15") (pintype "bidirectional"))
      (node (ref "V2") (pin "1") (pinfunction "1_1") (pintype "passive"))
    )
    (net (code "81") (name "V3") (class "Default")
      (node (ref "M3") (pin "15") (pinfunction "X2_15") (pintype "bidirectional"))
      (node (ref "V3") (pin "1") (pinfunction "1_1") (pintype "passive"))
    )
    (net (code "82") (name "V4") (class "Default")
      (node (ref "M1") (pin "11") (pinfunction "X3_11") (pintype "bidirectional"))
      (node (ref "V4") (pin "1") (pinfunction "1_1") (pintype "passive"))
    )
    (net (code "83") (name "V5") (class "Default")
      (node (ref "M2") (pin "11") (pinfunction "X3_11") (pintype "bidirectional"))
      (node (ref "V5") (pin "1") (pinfunction "1_1") (pintype "passive"))
    )
    (net (code "84") (name "V6") (class "Default")
      (node (ref "M3") (pin "11") (pinfunction "X3_11") (pintype "bidirectional"))
      (node (ref "V6") (pin "1") (pinfunction "1_1") (pintype "passive"))
    )
    (net (code "85") (name "WCT") (class "Default")
      (node (ref "M1") (pin "2") (pinfunction "Y2_2") (pintype "bidirectional"))
      (node (ref "M1") (pin "4") (pinfunction "Y3_4") (pintype "bidirectional"))
      (node (ref "M2") (pin "2") (pinfunction "Y2_2") (pintype "bidirectional"))
      (node (ref "M2") (pin "4") (pinfunction "Y3_4") (pintype "bidirectional"))
      (node (ref "M3") (pin "2") (pinfunction "Y2_2") (pintype "bidirectional"))
      (node (ref "M3") (pin "4") (pinfunction "Y3_4") (pintype "bidirectional"))
      (node (ref "R7") (pin "2") (pinfunction "2_2") (pintype "passive"))
      (node (ref "R8") (pin "2") (pinfunction "2_2") (pintype "passive"))
      (node (ref "R9") (pin "2") (pinfunction "2_2") (pintype "passive"))
    )
    (net (code "86") (name "unconnected-(E1-LO+-Pad12)") (class "Default")
      (node (ref "E1") (pin "12") (pinfunction "LO+_12") (pintype "bidirectional"))
    )
    (net (code "87") (name "unconnected-(E1-LO--Pad11)") (class "Default")
      (node (ref "E1") (pin "11") (pinfunction "LO-_11") (pintype "bidirectional"))
    )
    (net (code "88") (name "unconnected-(E2-LO+-Pad12)") (class "Default")
      (node (ref "E2") (pin "12") (pinfunction "LO+_12") (pintype "bidirectional"))
    )
    (net (code "89") (name "unconnected-(E2-LO--Pad11)") (class "Default")
      (node (ref "E2") (pin "11") (pinfunction "LO-_11") (pintype "bidirectional"))
    )
    (net (code "90") (name "unconnected-(E3-LO+-Pad12)") (class "Default")
      (node (ref "E3") (pin "12") (pinfunction "LO+_12") (pintype "bidirectional"))
    )
    (net (code "91") (name "unconnected-(E3-LO--Pad11)") (class "Default")
      (node (ref "E3") (pin "11") (pinfunction "LO-_11") (pintype "bidirectional"))
    )
    (net (code "92") (name "unconnected-(E4-LO+-Pad12)") (class "Default")
      (node (ref "E4") (pin "12") (pinfunction "LO+_12") (pintype "bidirectional"))
    )
    (net (code "93") (name "unconnected-(E4-LO--Pad11)") (class "Default")
      (node (ref "E4") (pin "11") (pinfunction "LO-_11") (pintype "bidirectional"))
    )
  )
)
